# Top.net
KiCad netlist of a schematic drawn in Altium Designer
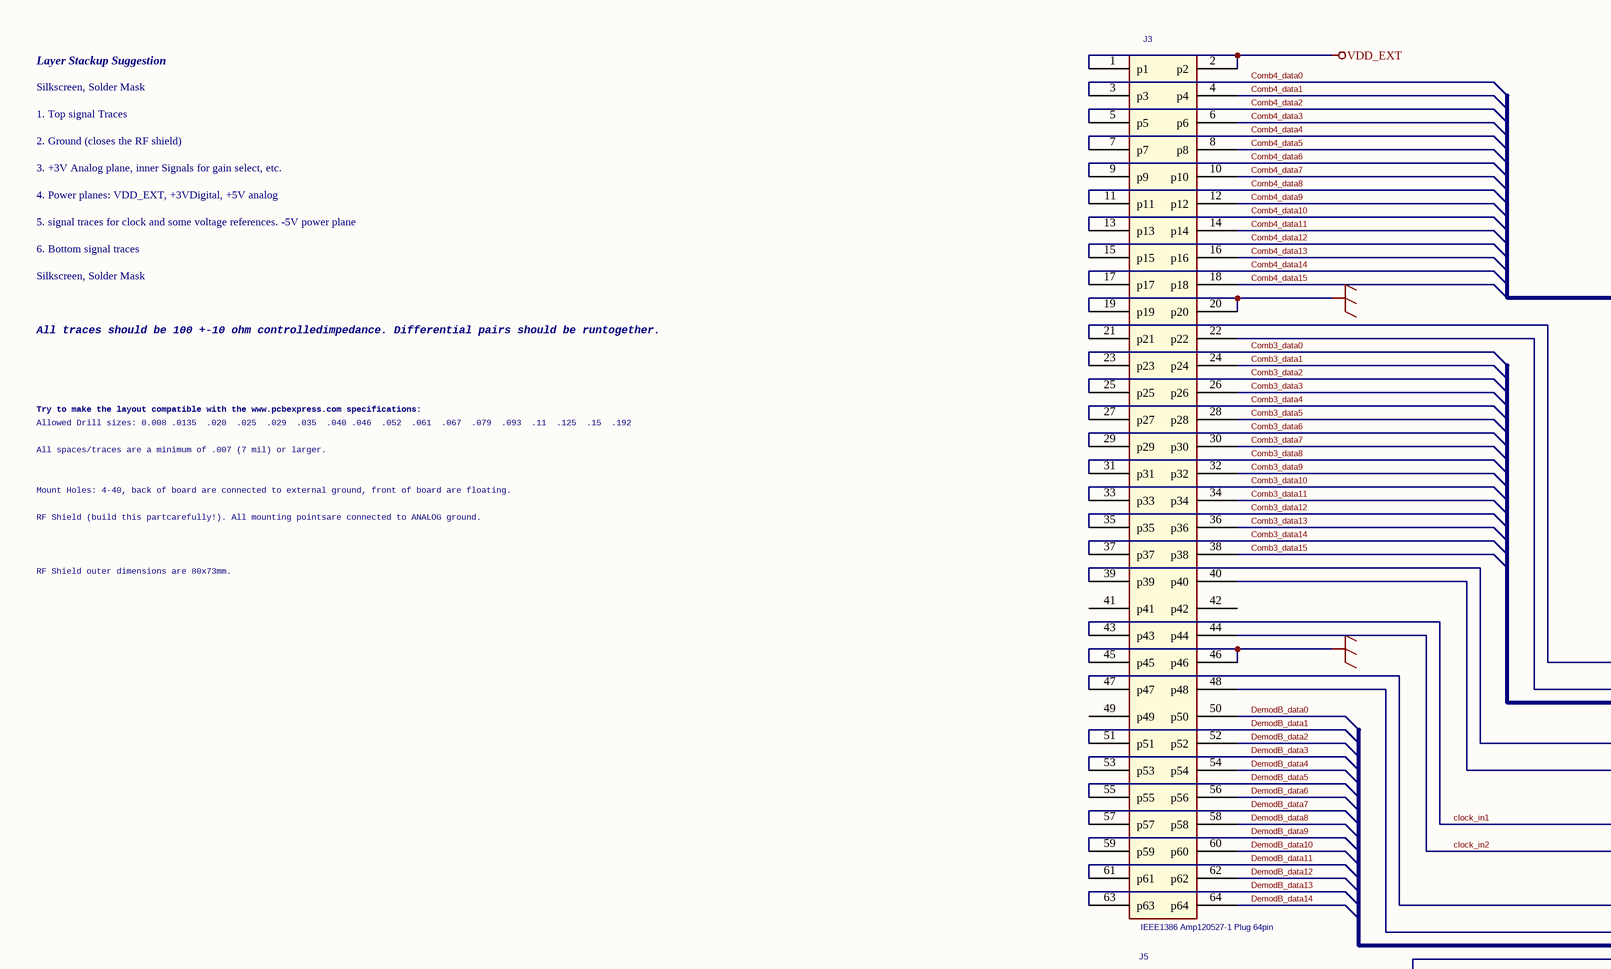
[diagram p0: Top.SchDoc, top left]
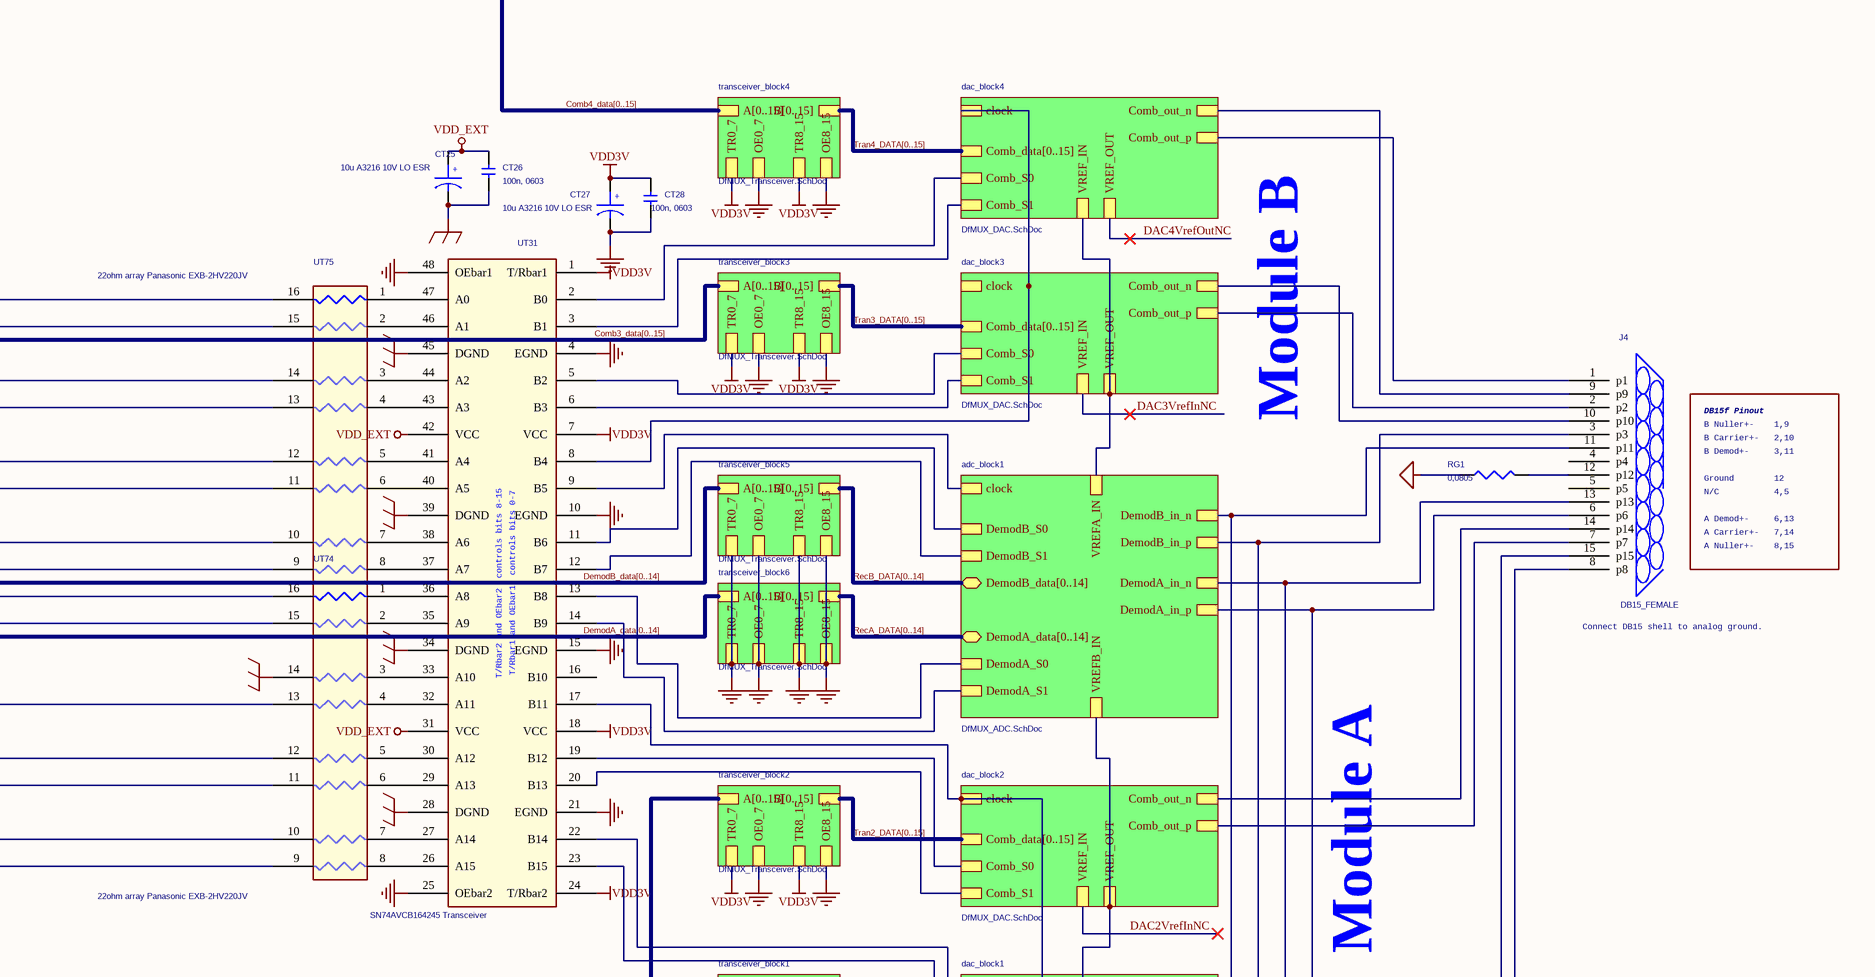
[diagram p1: Top.SchDoc, top right]
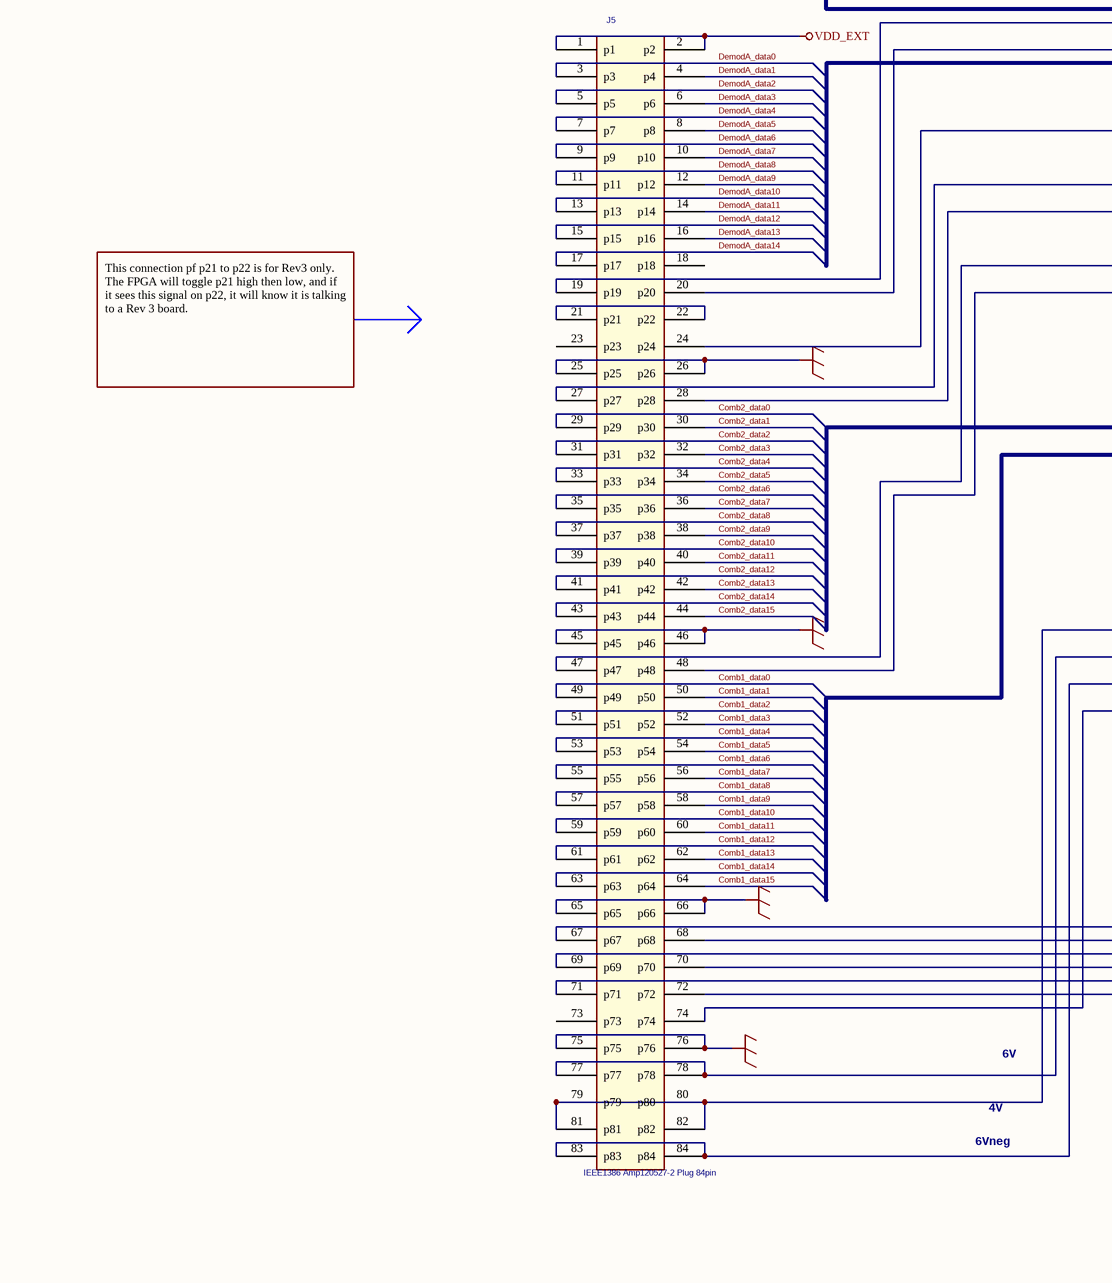
[diagram p2: Top.SchDoc, bottom left]
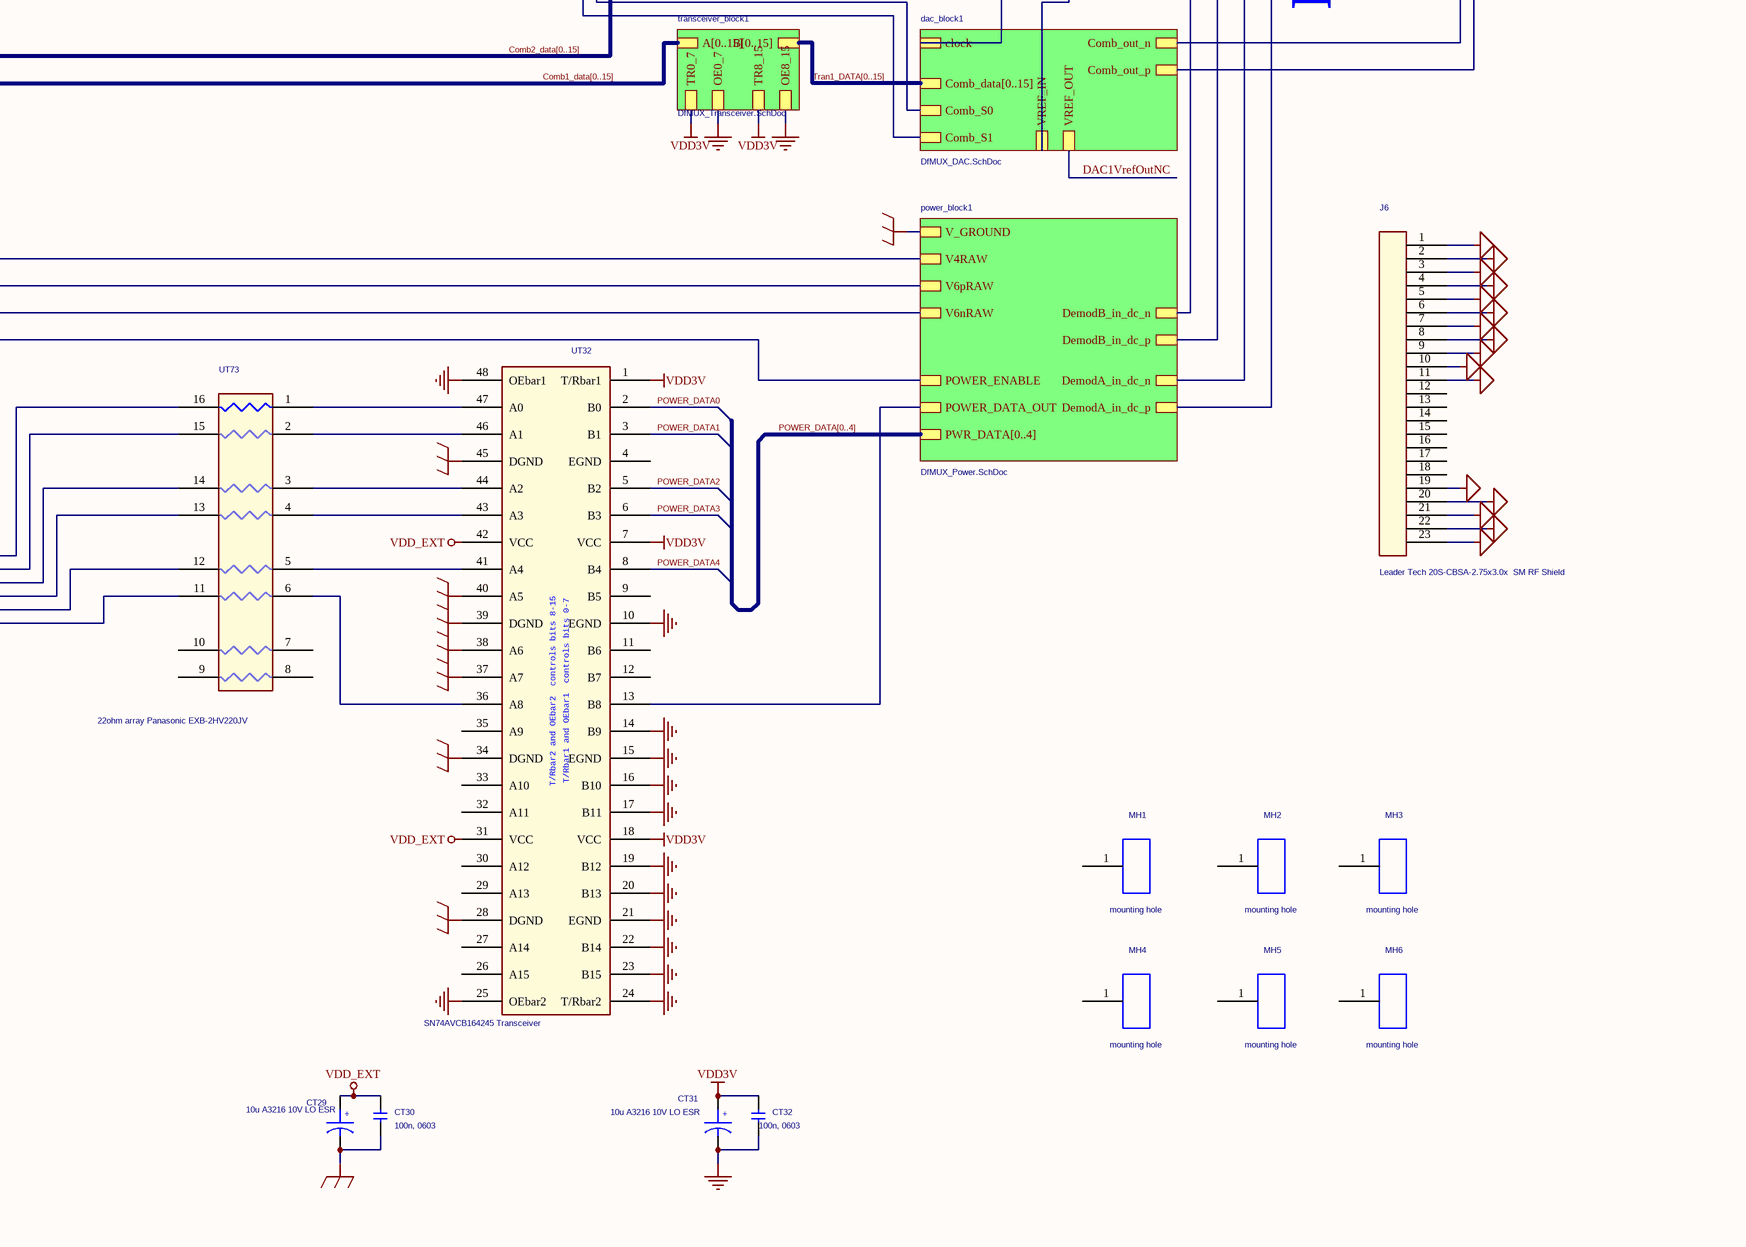
[diagram p3: Top.SchDoc, bottom right]

(export (version "E")
  (design (tool "Eeschema 10.0.6"))
  (components
    (comp (ref "CT25") (value "10u A3216 10V LO ESR") (libsource (lib "*") (part "CAPACITOR POL")))
    (comp (ref "CT26") (value "100n, 0603") (footprint "0603C") (libsource (lib "*") (part "C")))
    (comp (ref "CT27") (value "10u A3216 10V LO ESR") (libsource (lib "*") (part "CAPACITOR POL")))
    (comp (ref "CT28") (value "100n, 0603") (footprint "0603C") (libsource (lib "*") (part "C")))
    (comp (ref "CT29") (value "10u A3216 10V LO ESR") (libsource (lib "*") (part "CAPACITOR POL")))
    (comp (ref "CT30") (value "100n, 0603") (footprint "0603C") (libsource (lib "*") (part "C")))
    (comp (ref "CT31") (value "10u A3216 10V LO ESR") (libsource (lib "*") (part "CAPACITOR POL")))
    (comp (ref "CT32") (value "100n, 0603") (footprint "0603C") (libsource (lib "*") (part "C")))
    (comp (ref "J3")
      (value "IEEE1386 Amp120527-1 Plug 64pin")
      (libsource (lib "*") (part "IEEE1386 Amp120527-1 Plug 64pin"))
    )
    (comp (ref "J4") (value "DB15_FEMALE") (libsource (lib "*") (part "DB15_FEMALE")))
    (comp (ref "J5")
      (value "IEEE1386 Amp120527-2 Plug 84pin")
      (libsource (lib "*") (part "IEEE1386 Amp120527-2 Plug84pin"))
    )
    (comp (ref "J6")
      (value "Leader Tech 20S-CBSA-2.75x3.0x  SM RF Shield")
      (libsource (lib "*") (part "CONN FLEX 23"))
    )
    (comp (ref "MH1") (value "mounting hole") (libsource (lib "*") (part "SOUNDER_0")))
    (comp (ref "MH2") (value "mounting hole") (libsource (lib "*") (part "SOUNDER_0")))
    (comp (ref "MH3") (value "mounting hole") (libsource (lib "*") (part "SOUNDER_0")))
    (comp (ref "MH4") (value "mounting hole") (libsource (lib "*") (part "SOUNDER_0")))
    (comp (ref "MH5") (value "mounting hole") (libsource (lib "*") (part "SOUNDER_0")))
    (comp (ref "MH6") (value "mounting hole") (libsource (lib "*") (part "SOUNDER_0")))
    (comp (ref "RG1") (value "0,0805") (footprint "0805R") (libsource (lib "*") (part "R")))
    (comp (ref "UT31")
      (value "SN74AVCB164245 Transceiver")
      (libsource (lib "*") (part "74LVT16245 Transceiver_0"))
    )
    (comp (ref "UT32")
      (value "SN74AVCB164245 Transceiver")
      (libsource (lib "*") (part "74LVT16245 Transceiver_0"))
    )
    (comp (ref "UT73") (value "22ohm array Panasonic EXB-2HV220JV") (libsource (lib "*") (part "R-PACK_1")))
    (comp (ref "UT74") (value "22ohm array Panasonic EXB-2HV220JV") (libsource (lib "*") (part "R-PACK_1")))
    (comp (ref "UT75") (value "22ohm array Panasonic EXB-2HV220JV") (libsource (lib "*") (part "R-PACK_1")))
  )
  (nets
    (net (code "95") (name "/Comb1_data0") (class "Default")
      (node (ref "J5") (pin "49") (pinfunction "p49_49") (pintype "passive"))
    )
    (net (code "96") (name "/Comb1_data1") (class "Default")
      (node (ref "J5") (pin "50") (pinfunction "p50_50") (pintype "passive"))
    )
    (net (code "97") (name "/Comb1_data2") (class "Default")
      (node (ref "J5") (pin "51") (pinfunction "p51_51") (pintype "passive"))
    )
    (net (code "98") (name "/Comb1_data3") (class "Default")
      (node (ref "J5") (pin "52") (pinfunction "p52_52") (pintype "passive"))
    )
    (net (code "99") (name "/Comb1_data4") (class "Default")
      (node (ref "J5") (pin "53") (pinfunction "p53_53") (pintype "passive"))
    )
    (net (code "100") (name "/Comb1_data5") (class "Default")
      (node (ref "J5") (pin "54") (pinfunction "p54_54") (pintype "passive"))
    )
    (net (code "101") (name "/Comb1_data6") (class "Default")
      (node (ref "J5") (pin "55") (pinfunction "p55_55") (pintype "passive"))
    )
    (net (code "102") (name "/Comb1_data7") (class "Default")
      (node (ref "J5") (pin "56") (pinfunction "p56_56") (pintype "passive"))
    )
    (net (code "103") (name "/Comb1_data8") (class "Default")
      (node (ref "J5") (pin "57") (pinfunction "p57_57") (pintype "passive"))
    )
    (net (code "104") (name "/Comb1_data9") (class "Default")
      (node (ref "J5") (pin "58") (pinfunction "p58_58") (pintype "passive"))
    )
    (net (code "105") (name "/Comb1_data10") (class "Default")
      (node (ref "J5") (pin "59") (pinfunction "p59_59") (pintype "passive"))
    )
    (net (code "106") (name "/Comb1_data11") (class "Default")
      (node (ref "J5") (pin "60") (pinfunction "p60_60") (pintype "passive"))
    )
    (net (code "107") (name "/Comb1_data12") (class "Default")
      (node (ref "J5") (pin "61") (pinfunction "p61_61") (pintype "passive"))
    )
    (net (code "108") (name "/Comb1_data13") (class "Default")
      (node (ref "J5") (pin "62") (pinfunction "p62_62") (pintype "passive"))
    )
    (net (code "109") (name "/Comb1_data14") (class "Default")
      (node (ref "J5") (pin "63") (pinfunction "p63_63") (pintype "passive"))
    )
    (net (code "110") (name "/Comb1_data15") (class "Default")
      (node (ref "J5") (pin "64") (pinfunction "p64_64") (pintype "passive"))
    )
    (net (code "112") (name "/Comb2_data0") (class "Default")
      (node (ref "J5") (pin "29") (pinfunction "p29_29") (pintype "passive"))
    )
    (net (code "113") (name "/Comb2_data1") (class "Default")
      (node (ref "J5") (pin "30") (pinfunction "p30_30") (pintype "passive"))
    )
    (net (code "114") (name "/Comb2_data2") (class "Default")
      (node (ref "J5") (pin "31") (pinfunction "p31_31") (pintype "passive"))
    )
    (net (code "115") (name "/Comb2_data3") (class "Default")
      (node (ref "J5") (pin "32") (pinfunction "p32_32") (pintype "passive"))
    )
    (net (code "116") (name "/Comb2_data4") (class "Default")
      (node (ref "J5") (pin "33") (pinfunction "p33_33") (pintype "passive"))
    )
    (net (code "117") (name "/Comb2_data5") (class "Default")
      (node (ref "J5") (pin "34") (pinfunction "p34_34") (pintype "passive"))
    )
    (net (code "118") (name "/Comb2_data6") (class "Default")
      (node (ref "J5") (pin "35") (pinfunction "p35_35") (pintype "passive"))
    )
    (net (code "119") (name "/Comb2_data7") (class "Default")
      (node (ref "J5") (pin "36") (pinfunction "p36_36") (pintype "passive"))
    )
    (net (code "120") (name "/Comb2_data8") (class "Default")
      (node (ref "J5") (pin "37") (pinfunction "p37_37") (pintype "passive"))
    )
    (net (code "121") (name "/Comb2_data9") (class "Default")
      (node (ref "J5") (pin "38") (pinfunction "p38_38") (pintype "passive"))
    )
    (net (code "122") (name "/Comb2_data10") (class "Default")
      (node (ref "J5") (pin "39") (pinfunction "p39_39") (pintype "passive"))
    )
    (net (code "123") (name "/Comb2_data11") (class "Default")
      (node (ref "J5") (pin "40") (pinfunction "p40_40") (pintype "passive"))
    )
    (net (code "124") (name "/Comb2_data12") (class "Default")
      (node (ref "J5") (pin "41") (pinfunction "p41_41") (pintype "passive"))
    )
    (net (code "125") (name "/Comb2_data13") (class "Default")
      (node (ref "J5") (pin "42") (pinfunction "p42_42") (pintype "passive"))
    )
    (net (code "126") (name "/Comb2_data14") (class "Default")
      (node (ref "J5") (pin "43") (pinfunction "p43_43") (pintype "passive"))
    )
    (net (code "127") (name "/Comb2_data15") (class "Default")
      (node (ref "J5") (pin "44") (pinfunction "p44_44") (pintype "passive"))
    )
    (net (code "129") (name "/Comb3_data0") (class "Default")
      (node (ref "J3") (pin "23") (pinfunction "p23_23") (pintype "passive"))
    )
    (net (code "130") (name "/Comb3_data1") (class "Default")
      (node (ref "J3") (pin "24") (pinfunction "p24_24") (pintype "passive"))
    )
    (net (code "131") (name "/Comb3_data2") (class "Default")
      (node (ref "J3") (pin "25") (pinfunction "p25_25") (pintype "passive"))
    )
    (net (code "132") (name "/Comb3_data3") (class "Default")
      (node (ref "J3") (pin "26") (pinfunction "p26_26") (pintype "passive"))
    )
    (net (code "133") (name "/Comb3_data4") (class "Default")
      (node (ref "J3") (pin "27") (pinfunction "p27_27") (pintype "passive"))
    )
    (net (code "134") (name "/Comb3_data5") (class "Default")
      (node (ref "J3") (pin "28") (pinfunction "p28_28") (pintype "passive"))
    )
    (net (code "135") (name "/Comb3_data6") (class "Default")
      (node (ref "J3") (pin "29") (pinfunction "p29_29") (pintype "passive"))
    )
    (net (code "136") (name "/Comb3_data7") (class "Default")
      (node (ref "J3") (pin "30") (pinfunction "p30_30") (pintype "passive"))
    )
    (net (code "137") (name "/Comb3_data8") (class "Default")
      (node (ref "J3") (pin "31") (pinfunction "p31_31") (pintype "passive"))
    )
    (net (code "138") (name "/Comb3_data9") (class "Default")
      (node (ref "J3") (pin "32") (pinfunction "p32_32") (pintype "passive"))
    )
    (net (code "139") (name "/Comb3_data10") (class "Default")
      (node (ref "J3") (pin "33") (pinfunction "p33_33") (pintype "passive"))
    )
    (net (code "140") (name "/Comb3_data11") (class "Default")
      (node (ref "J3") (pin "34") (pinfunction "p34_34") (pintype "passive"))
    )
    (net (code "141") (name "/Comb3_data12") (class "Default")
      (node (ref "J3") (pin "35") (pinfunction "p35_35") (pintype "passive"))
    )
    (net (code "142") (name "/Comb3_data13") (class "Default")
      (node (ref "J3") (pin "36") (pinfunction "p36_36") (pintype "passive"))
    )
    (net (code "143") (name "/Comb3_data14") (class "Default")
      (node (ref "J3") (pin "37") (pinfunction "p37_37") (pintype "passive"))
    )
    (net (code "144") (name "/Comb3_data15") (class "Default")
      (node (ref "J3") (pin "38") (pinfunction "p38_38") (pintype "passive"))
    )
    (net (code "146") (name "/Comb4_data0") (class "Default")
      (node (ref "J3") (pin "3") (pinfunction "p3_3") (pintype "passive"))
    )
    (net (code "147") (name "/Comb4_data1") (class "Default")
      (node (ref "J3") (pin "4") (pinfunction "p4_4") (pintype "passive"))
    )
    (net (code "148") (name "/Comb4_data2") (class "Default")
      (node (ref "J3") (pin "5") (pinfunction "p5_5") (pintype "passive"))
    )
    (net (code "149") (name "/Comb4_data3") (class "Default")
      (node (ref "J3") (pin "6") (pinfunction "p6_6") (pintype "passive"))
    )
    (net (code "150") (name "/Comb4_data4") (class "Default")
      (node (ref "J3") (pin "7") (pinfunction "p7_7") (pintype "passive"))
    )
    (net (code "151") (name "/Comb4_data5") (class "Default")
      (node (ref "J3") (pin "8") (pinfunction "p8_8") (pintype "passive"))
    )
    (net (code "152") (name "/Comb4_data6") (class "Default")
      (node (ref "J3") (pin "9") (pinfunction "p9_9") (pintype "passive"))
    )
    (net (code "153") (name "/Comb4_data7") (class "Default")
      (node (ref "J3") (pin "10") (pinfunction "p10_10") (pintype "passive"))
    )
    (net (code "154") (name "/Comb4_data8") (class "Default")
      (node (ref "J3") (pin "11") (pinfunction "p11_11") (pintype "passive"))
    )
    (net (code "155") (name "/Comb4_data9") (class "Default")
      (node (ref "J3") (pin "12") (pinfunction "p12_12") (pintype "passive"))
    )
    (net (code "156") (name "/Comb4_data10") (class "Default")
      (node (ref "J3") (pin "13") (pinfunction "p13_13") (pintype "passive"))
    )
    (net (code "157") (name "/Comb4_data11") (class "Default")
      (node (ref "J3") (pin "14") (pinfunction "p14_14") (pintype "passive"))
    )
    (net (code "158") (name "/Comb4_data12") (class "Default")
      (node (ref "J3") (pin "15") (pinfunction "p15_15") (pintype "passive"))
    )
    (net (code "159") (name "/Comb4_data13") (class "Default")
      (node (ref "J3") (pin "16") (pinfunction "p16_16") (pintype "passive"))
    )
    (net (code "160") (name "/Comb4_data14") (class "Default")
      (node (ref "J3") (pin "17") (pinfunction "p17_17") (pintype "passive"))
    )
    (net (code "161") (name "/Comb4_data15") (class "Default")
      (node (ref "J3") (pin "18") (pinfunction "p18_18") (pintype "passive"))
    )
    (net (code "163") (name "/Comb_S0") (class "Default")
      (node (ref "UT31") (pin "19") (pinfunction "B12_19") (pintype "passive"))
    )
    (net (code "164") (name "/Comb_S0_1") (class "Default")
      (node (ref "UT31") (pin "2") (pinfunction "B0_2") (pintype "passive"))
    )
    (net (code "165") (name "/Comb_S0_2") (class "Default")
      (node (ref "UT31") (pin "5") (pinfunction "B2_5") (pintype "passive"))
    )
    (net (code "166") (name "/Comb_S0_3") (class "Default")
      (node (ref "UT31") (pin "22") (pinfunction "B14_22") (pintype "passive"))
    )
    (net (code "167") (name "/Comb_S1") (class "Default")
      (node (ref "UT31") (pin "20") (pinfunction "B13_20") (pintype "passive"))
    )
    (net (code "168") (name "/Comb_S1_1") (class "Default")
      (node (ref "UT31") (pin "3") (pinfunction "B1_3") (pintype "passive"))
    )
    (net (code "169") (name "/Comb_S1_2") (class "Default")
      (node (ref "UT31") (pin "23") (pinfunction "B15_23") (pintype "passive"))
    )
    (net (code "170") (name "/Comb_S1_3") (class "Default")
      (node (ref "UT31") (pin "6") (pinfunction "B3_6") (pintype "passive"))
    )
    (net (code "171") (name "/Comb_out_n") (class "Default")
      (node (ref "J4") (pin "15") (pinfunction "p15_15") (pintype "passive"))
    )
    (net (code "172") (name "/Comb_out_n_1") (class "Default")
      (node (ref "J4") (pin "9") (pinfunction "p9_9") (pintype "passive"))
    )
    (net (code "173") (name "/Comb_out_n_2") (class "Default")
      (node (ref "J4") (pin "10") (pinfunction "p10_10") (pintype "passive"))
    )
    (net (code "174") (name "/Comb_out_n_3") (class "Default")
      (node (ref "J4") (pin "14") (pinfunction "p14_14") (pintype "passive"))
    )
    (net (code "175") (name "/Comb_out_p") (class "Default")
      (node (ref "J4") (pin "8") (pinfunction "p8_8") (pintype "passive"))
    )
    (net (code "176") (name "/Comb_out_p_1") (class "Default")
      (node (ref "J4") (pin "1") (pinfunction "p1_1") (pintype "passive"))
    )
    (net (code "177") (name "/Comb_out_p_2") (class "Default")
      (node (ref "J4") (pin "2") (pinfunction "p2_2") (pintype "passive"))
    )
    (net (code "178") (name "/Comb_out_p_3") (class "Default")
      (node (ref "J4") (pin "7") (pinfunction "p7_7") (pintype "passive"))
    )
    (net (code "183") (name "/DemodA_S0") (class "Default")
      (node (ref "UT31") (pin "13") (pinfunction "B8_13") (pintype "passive"))
    )
    (net (code "184") (name "/DemodA_S1") (class "Default")
      (node (ref "UT31") (pin "14") (pinfunction "B9_14") (pintype "passive"))
    )
    (net (code "185") (name "/DemodA_data0") (class "Default")
      (node (ref "J5") (pin "3") (pinfunction "p3_3") (pintype "passive"))
    )
    (net (code "186") (name "/DemodA_data1") (class "Default")
      (node (ref "J5") (pin "4") (pinfunction "p4_4") (pintype "passive"))
    )
    (net (code "187") (name "/DemodA_data2") (class "Default")
      (node (ref "J5") (pin "5") (pinfunction "p5_5") (pintype "passive"))
    )
    (net (code "188") (name "/DemodA_data3") (class "Default")
      (node (ref "J5") (pin "6") (pinfunction "p6_6") (pintype "passive"))
    )
    (net (code "189") (name "/DemodA_data4") (class "Default")
      (node (ref "J5") (pin "7") (pinfunction "p7_7") (pintype "passive"))
    )
    (net (code "190") (name "/DemodA_data5") (class "Default")
      (node (ref "J5") (pin "8") (pinfunction "p8_8") (pintype "passive"))
    )
    (net (code "191") (name "/DemodA_data6") (class "Default")
      (node (ref "J5") (pin "9") (pinfunction "p9_9") (pintype "passive"))
    )
    (net (code "192") (name "/DemodA_data7") (class "Default")
      (node (ref "J5") (pin "10") (pinfunction "p10_10") (pintype "passive"))
    )
    (net (code "193") (name "/DemodA_data8") (class "Default")
      (node (ref "J5") (pin "11") (pinfunction "p11_11") (pintype "passive"))
    )
    (net (code "194") (name "/DemodA_data9") (class "Default")
      (node (ref "J5") (pin "12") (pinfunction "p12_12") (pintype "passive"))
    )
    (net (code "195") (name "/DemodA_data10") (class "Default")
      (node (ref "J5") (pin "13") (pinfunction "p13_13") (pintype "passive"))
    )
    (net (code "196") (name "/DemodA_data11") (class "Default")
      (node (ref "J5") (pin "14") (pinfunction "p14_14") (pintype "passive"))
    )
    (net (code "197") (name "/DemodA_data12") (class "Default")
      (node (ref "J5") (pin "15") (pinfunction "p15_15") (pintype "passive"))
    )
    (net (code "198") (name "/DemodA_data13") (class "Default")
      (node (ref "J5") (pin "16") (pinfunction "p16_16") (pintype "passive"))
    )
    (net (code "199") (name "/DemodA_data14") (class "Default")
      (node (ref "J5") (pin "17") (pinfunction "p17_17") (pintype "passive"))
    )
    (net (code "201") (name "/DemodA_in_dc_n") (class "Default")
      (node (ref "J4") (pin "13") (pinfunction "p13_13") (pintype "passive"))
    )
    (net (code "202") (name "/DemodA_in_dc_p") (class "Default")
      (node (ref "J4") (pin "6") (pinfunction "p6_6") (pintype "passive"))
    )
    (net (code "203") (name "/DemodB_S0") (class "Default")
      (node (ref "UT31") (pin "11") (pinfunction "B6_11") (pintype "passive"))
    )
    (net (code "204") (name "/DemodB_S1") (class "Default")
      (node (ref "UT31") (pin "12") (pinfunction "B7_12") (pintype "passive"))
    )
    (net (code "205") (name "/DemodB_data0") (class "Default")
      (node (ref "J3") (pin "50") (pinfunction "p50_50") (pintype "passive"))
    )
    (net (code "206") (name "/DemodB_data1") (class "Default")
      (node (ref "J3") (pin "51") (pinfunction "p51_51") (pintype "passive"))
    )
    (net (code "207") (name "/DemodB_data2") (class "Default")
      (node (ref "J3") (pin "52") (pinfunction "p52_52") (pintype "passive"))
    )
    (net (code "208") (name "/DemodB_data3") (class "Default")
      (node (ref "J3") (pin "53") (pinfunction "p53_53") (pintype "passive"))
    )
    (net (code "209") (name "/DemodB_data4") (class "Default")
      (node (ref "J3") (pin "54") (pinfunction "p54_54") (pintype "passive"))
    )
    (net (code "210") (name "/DemodB_data5") (class "Default")
      (node (ref "J3") (pin "55") (pinfunction "p55_55") (pintype "passive"))
    )
    (net (code "211") (name "/DemodB_data6") (class "Default")
      (node (ref "J3") (pin "56") (pinfunction "p56_56") (pintype "passive"))
    )
    (net (code "212") (name "/DemodB_data7") (class "Default")
      (node (ref "J3") (pin "57") (pinfunction "p57_57") (pintype "passive"))
    )
    (net (code "213") (name "/DemodB_data8") (class "Default")
      (node (ref "J3") (pin "58") (pinfunction "p58_58") (pintype "passive"))
    )
    (net (code "214") (name "/DemodB_data9") (class "Default")
      (node (ref "J3") (pin "59") (pinfunction "p59_59") (pintype "passive"))
    )
    (net (code "215") (name "/DemodB_data10") (class "Default")
      (node (ref "J3") (pin "60") (pinfunction "p60_60") (pintype "passive"))
    )
    (net (code "216") (name "/DemodB_data11") (class "Default")
      (node (ref "J3") (pin "61") (pinfunction "p61_61") (pintype "passive"))
    )
    (net (code "217") (name "/DemodB_data12") (class "Default")
      (node (ref "J3") (pin "62") (pinfunction "p62_62") (pintype "passive"))
    )
    (net (code "218") (name "/DemodB_data13") (class "Default")
      (node (ref "J3") (pin "63") (pinfunction "p63_63") (pintype "passive"))
    )
    (net (code "219") (name "/DemodB_data14") (class "Default")
      (node (ref "J3") (pin "64") (pinfunction "p64_64") (pintype "passive"))
    )
    (net (code "221") (name "/DemodB_in_dc_n") (class "Default")
      (node (ref "J4") (pin "11") (pinfunction "p11_11") (pintype "passive"))
    )
    (net (code "222") (name "/DemodB_in_dc_p") (class "Default")
      (node (ref "J4") (pin "3") (pinfunction "p3_3") (pintype "passive"))
    )
    (net (code "223") (name "/POWER_DATA0") (class "Default")
      (node (ref "UT32") (pin "2") (pinfunction "B0_2") (pintype "passive"))
    )
    (net (code "224") (name "/POWER_DATA1") (class "Default")
      (node (ref "UT32") (pin "3") (pinfunction "B1_3") (pintype "passive"))
    )
    (net (code "225") (name "/POWER_DATA2") (class "Default")
      (node (ref "UT32") (pin "5") (pinfunction "B2_5") (pintype "passive"))
    )
    (net (code "226") (name "/POWER_DATA3") (class "Default")
      (node (ref "UT32") (pin "6") (pinfunction "B3_6") (pintype "passive"))
    )
    (net (code "227") (name "/POWER_DATA4") (class "Default")
      (node (ref "UT32") (pin "8") (pinfunction "B4_8") (pintype "passive"))
    )
    (net (code "229") (name "/POWER_DATA_OUT") (class "Default")
      (node (ref "UT32") (pin "13") (pinfunction "B8_13") (pintype "passive"))
    )
    (net (code "230") (name "/POWER_ENABLE") (class "Default")
      (node (ref "J5") (pin "74") (pinfunction "p74_74") (pintype "passive"))
    )
    (net (code "237") (name "/V4RAW") (class "Default")
      (node (ref "J5") (pin "79") (pinfunction "p79_79") (pintype "passive"))
      (node (ref "J5") (pin "80") (pinfunction "p80_80") (pintype "passive"))
      (node (ref "J5") (pin "81") (pinfunction "p81_81") (pintype "passive"))
      (node (ref "J5") (pin "82") (pinfunction "p82_82") (pintype "passive"))
    )
    (net (code "238") (name "/V6nRAW") (class "Default")
      (node (ref "J5") (pin "83") (pinfunction "p83_83") (pintype "passive"))
      (node (ref "J5") (pin "84") (pinfunction "p84_84") (pintype "passive"))
    )
    (net (code "239") (name "/V6pRAW") (class "Default")
      (node (ref "J5") (pin "77") (pinfunction "p77_77") (pintype "passive"))
      (node (ref "J5") (pin "78") (pinfunction "p78_78") (pintype "passive"))
    )
    (net (code "242") (name "/clock") (class "Default")
      (node (ref "UT31") (pin "8") (pinfunction "B4_8") (pintype "passive"))
    )
    (net (code "243") (name "/clock_1") (class "Default")
      (node (ref "UT31") (pin "17") (pinfunction "B11_17") (pintype "passive"))
    )
    (net (code "244") (name "/clock_2") (class "Default")
      (node (ref "UT31") (pin "9") (pinfunction "B5_9") (pintype "passive"))
    )
    (net (code "245") (name "/clock_in1") (class "Default")
      (node (ref "J3") (pin "43") (pinfunction "p43_43") (pintype "passive"))
      (node (ref "UT75") (pin "12") (pinfunction "R5_12") (pintype "passive"))
    )
    (net (code "246") (name "/clock_in2") (class "Default")
      (node (ref "J3") (pin "44") (pinfunction "p44_44") (pintype "passive"))
      (node (ref "UT75") (pin "11") (pinfunction "R6_11") (pintype "passive"))
    )
    (net (code "247") (name "GND_DIG") (class "Default")
      (node (ref "CT27") (pin "2") (pinfunction "2_2") (pintype "passive"))
      (node (ref "CT28") (pin "1") (pinfunction "1_1") (pintype "passive"))
      (node (ref "CT31") (pin "2") (pinfunction "2_2") (pintype "passive"))
      (node (ref "CT32") (pin "1") (pinfunction "1_1") (pintype "passive"))
      (node (ref "UT31") (pin "10") (pinfunction "EGND_10") (pintype "passive"))
      (node (ref "UT31") (pin "15") (pinfunction "EGND_15") (pintype "passive"))
      (node (ref "UT31") (pin "21") (pinfunction "EGND_21") (pintype "passive"))
      (node (ref "UT31") (pin "25") (pinfunction "OEbar2_25") (pintype "passive"))
      (node (ref "UT31") (pin "4") (pinfunction "EGND_4") (pintype "passive"))
      (node (ref "UT31") (pin "48") (pinfunction "OEbar1_48") (pintype "passive"))
      (node (ref "UT32") (pin "10") (pinfunction "EGND_10") (pintype "passive"))
      (node (ref "UT32") (pin "14") (pinfunction "B9_14") (pintype "passive"))
      (node (ref "UT32") (pin "15") (pinfunction "EGND_15") (pintype "passive"))
      (node (ref "UT32") (pin "16") (pinfunction "B10_16") (pintype "passive"))
      (node (ref "UT32") (pin "17") (pinfunction "B11_17") (pintype "passive"))
      (node (ref "UT32") (pin "19") (pinfunction "B12_19") (pintype "passive"))
      (node (ref "UT32") (pin "20") (pinfunction "B13_20") (pintype "passive"))
      (node (ref "UT32") (pin "21") (pinfunction "EGND_21") (pintype "passive"))
      (node (ref "UT32") (pin "22") (pinfunction "B14_22") (pintype "passive"))
      (node (ref "UT32") (pin "23") (pinfunction "B15_23") (pintype "passive"))
      (node (ref "UT32") (pin "24") (pinfunction "T/Rbar2_24") (pintype "passive"))
      (node (ref "UT32") (pin "25") (pinfunction "OEbar2_25") (pintype "passive"))
      (node (ref "UT32") (pin "48") (pinfunction "OEbar1_48") (pintype "passive"))
    )
    (net (code "248") (name "GND_EARTH") (class "Default")
      (node (ref "CT25") (pin "2") (pinfunction "2_2") (pintype "passive"))
      (node (ref "CT26") (pin "1") (pinfunction "1_1") (pintype "passive"))
      (node (ref "CT29") (pin "2") (pinfunction "2_2") (pintype "passive"))
      (node (ref "CT30") (pin "1") (pinfunction "1_1") (pintype "passive"))
      (node (ref "J3") (pin "19") (pinfunction "p19_19") (pintype "passive"))
      (node (ref "J3") (pin "20") (pinfunction "p20_20") (pintype "passive"))
      (node (ref "J3") (pin "45") (pinfunction "p45_45") (pintype "passive"))
      (node (ref "J3") (pin "46") (pinfunction "p46_46") (pintype "passive"))
      (node (ref "J5") (pin "25") (pinfunction "p25_25") (pintype "passive"))
      (node (ref "J5") (pin "26") (pinfunction "p26_26") (pintype "passive"))
      (node (ref "J5") (pin "45") (pinfunction "p45_45") (pintype "passive"))
      (node (ref "J5") (pin "46") (pinfunction "p46_46") (pintype "passive"))
      (node (ref "J5") (pin "65") (pinfunction "p65_65") (pintype "passive"))
      (node (ref "J5") (pin "66") (pinfunction "p66_66") (pintype "passive"))
      (node (ref "J5") (pin "75") (pinfunction "p75_75") (pintype "passive"))
      (node (ref "J5") (pin "76") (pinfunction "p76_76") (pintype "passive"))
      (node (ref "UT31") (pin "28") (pinfunction "DGND_28") (pintype "passive"))
      (node (ref "UT31") (pin "34") (pinfunction "DGND_34") (pintype "passive"))
      (node (ref "UT31") (pin "39") (pinfunction "DGND_39") (pintype "passive"))
      (node (ref "UT31") (pin "45") (pinfunction "DGND_45") (pintype "passive"))
      (node (ref "UT32") (pin "28") (pinfunction "DGND_28") (pintype "passive"))
      (node (ref "UT32") (pin "34") (pinfunction "DGND_34") (pintype "passive"))
      (node (ref "UT32") (pin "37") (pinfunction "A7_37") (pintype "passive"))
      (node (ref "UT32") (pin "38") (pinfunction "A6_38") (pintype "passive"))
      (node (ref "UT32") (pin "39") (pinfunction "DGND_39") (pintype "passive"))
      (node (ref "UT32") (pin "40") (pinfunction "A5_40") (pintype "passive"))
      (node (ref "UT32") (pin "45") (pinfunction "DGND_45") (pintype "passive"))
      (node (ref "UT74") (pin "14") (pinfunction "R3_14") (pintype "passive"))
    )
    (net (code "249") (name "GND_SIGNAL") (class "Default")
      (node (ref "J6") (pin "1") (pinfunction "1_1") (pintype "passive"))
      (node (ref "J6") (pin "10") (pinfunction "10_10") (pintype "passive"))
      (node (ref "J6") (pin "11") (pinfunction "11_11") (pintype "passive"))
      (node (ref "J6") (pin "19") (pinfunction "19_19") (pintype "passive"))
      (node (ref "J6") (pin "2") (pinfunction "2_2") (pintype "passive"))
      (node (ref "J6") (pin "20") (pinfunction "20_20") (pintype "passive"))
      (node (ref "J6") (pin "21") (pinfunction "21_21") (pintype "passive"))
      (node (ref "J6") (pin "22") (pinfunction "22_22") (pintype "passive"))
      (node (ref "J6") (pin "23") (pinfunction "23_23") (pintype "passive"))
      (node (ref "J6") (pin "3") (pinfunction "3_3") (pintype "passive"))
      (node (ref "J6") (pin "4") (pinfunction "4_4") (pintype "passive"))
      (node (ref "J6") (pin "5") (pinfunction "5_5") (pintype "passive"))
      (node (ref "J6") (pin "6") (pinfunction "6_6") (pintype "passive"))
      (node (ref "J6") (pin "7") (pinfunction "7_7") (pintype "passive"))
      (node (ref "J6") (pin "8") (pinfunction "8_8") (pintype "passive"))
      (node (ref "J6") (pin "9") (pinfunction "9_9") (pintype "passive"))
      (node (ref "RG1") (pin "1") (pinfunction "1_1") (pintype "passive"))
    )
    (net (code "250") (name "Net-(J3-p21)") (class "Default")
      (node (ref "J3") (pin "21") (pinfunction "p21_21") (pintype "passive"))
      (node (ref "UT75") (pin "16") (pinfunction "R1_16") (pintype "passive"))
    )
    (net (code "251") (name "Net-(J3-p22)") (class "Default")
      (node (ref "J3") (pin "22") (pinfunction "p22_22") (pintype "passive"))
      (node (ref "UT75") (pin "15") (pinfunction "R2_15") (pintype "passive"))
    )
    (net (code "252") (name "Net-(J3-p39)") (class "Default")
      (node (ref "J3") (pin "39") (pinfunction "p39_39") (pintype "passive"))
      (node (ref "UT75") (pin "14") (pinfunction "R3_14") (pintype "passive"))
    )
    (net (code "253") (name "Net-(J3-p40)") (class "Default")
      (node (ref "J3") (pin "40") (pinfunction "p40_40") (pintype "passive"))
      (node (ref "UT75") (pin "13") (pinfunction "R4_13") (pintype "passive"))
    )
    (net (code "254") (name "Net-(J3-p47)") (class "Default")
      (node (ref "J3") (pin "47") (pinfunction "p47_47") (pintype "passive"))
      (node (ref "UT75") (pin "10") (pinfunction "R7_10") (pintype "passive"))
    )
    (net (code "255") (name "Net-(J3-p48)") (class "Default")
      (node (ref "J3") (pin "48") (pinfunction "p48_48") (pintype "passive"))
      (node (ref "UT75") (pin "9") (pinfunction "R8_9") (pintype "passive"))
    )
    (net (code "256") (name "Net-(J4-p12)") (class "Default")
      (node (ref "J4") (pin "12") (pinfunction "p12_12") (pintype "passive"))
      (node (ref "RG1") (pin "2") (pinfunction "2_2") (pintype "passive"))
    )
    (net (code "257") (name "Net-(J5-p19)") (class "Default")
      (node (ref "J5") (pin "19") (pinfunction "p19_19") (pintype "passive"))
      (node (ref "UT74") (pin "16") (pinfunction "R1_16") (pintype "passive"))
    )
    (net (code "258") (name "Net-(J5-p20)") (class "Default")
      (node (ref "J5") (pin "20") (pinfunction "p20_20") (pintype "passive"))
      (node (ref "UT74") (pin "15") (pinfunction "R2_15") (pintype "passive"))
    )
    (net (code "259") (name "Net-(J5-p21)") (class "Default")
      (node (ref "J5") (pin "21") (pinfunction "p21_21") (pintype "passive"))
      (node (ref "J5") (pin "22") (pinfunction "p22_22") (pintype "passive"))
    )
    (net (code "260") (name "Net-(J5-p24)") (class "Default")
      (node (ref "J5") (pin "24") (pinfunction "p24_24") (pintype "passive"))
      (node (ref "UT74") (pin "13") (pinfunction "R4_13") (pintype "passive"))
    )
    (net (code "261") (name "Net-(J5-p27)") (class "Default")
      (node (ref "J5") (pin "27") (pinfunction "p27_27") (pintype "passive"))
      (node (ref "UT74") (pin "12") (pinfunction "R5_12") (pintype "passive"))
    )
    (net (code "262") (name "Net-(J5-p28)") (class "Default")
      (node (ref "J5") (pin "28") (pinfunction "p28_28") (pintype "passive"))
      (node (ref "UT74") (pin "11") (pinfunction "R6_11") (pintype "passive"))
    )
    (net (code "263") (name "Net-(J5-p47)") (class "Default")
      (node (ref "J5") (pin "47") (pinfunction "p47_47") (pintype "passive"))
      (node (ref "UT74") (pin "10") (pinfunction "R7_10") (pintype "passive"))
    )
    (net (code "264") (name "Net-(J5-p48)") (class "Default")
      (node (ref "J5") (pin "48") (pinfunction "p48_48") (pintype "passive"))
      (node (ref "UT74") (pin "9") (pinfunction "R8_9") (pintype "passive"))
    )
    (net (code "265") (name "Net-(J5-p67)") (class "Default")
      (node (ref "J5") (pin "67") (pinfunction "p67_67") (pintype "passive"))
      (node (ref "UT73") (pin "16") (pinfunction "R1_16") (pintype "passive"))
    )
    (net (code "266") (name "Net-(J5-p68)") (class "Default")
      (node (ref "J5") (pin "68") (pinfunction "p68_68") (pintype "passive"))
      (node (ref "UT73") (pin "15") (pinfunction "R2_15") (pintype "passive"))
    )
    (net (code "267") (name "Net-(J5-p69)") (class "Default")
      (node (ref "J5") (pin "69") (pinfunction "p69_69") (pintype "passive"))
      (node (ref "UT73") (pin "14") (pinfunction "R3_14") (pintype "passive"))
    )
    (net (code "268") (name "Net-(J5-p70)") (class "Default")
      (node (ref "J5") (pin "70") (pinfunction "p70_70") (pintype "passive"))
      (node (ref "UT73") (pin "13") (pinfunction "R4_13") (pintype "passive"))
    )
    (net (code "269") (name "Net-(J5-p71)") (class "Default")
      (node (ref "J5") (pin "71") (pinfunction "p71_71") (pintype "passive"))
      (node (ref "UT73") (pin "12") (pinfunction "R5_12") (pintype "passive"))
    )
    (net (code "270") (name "Net-(J5-p72)") (class "Default")
      (node (ref "J5") (pin "72") (pinfunction "p72_72") (pintype "passive"))
      (node (ref "UT73") (pin "11") (pinfunction "R6_11") (pintype "passive"))
    )
    (net (code "271") (name "Net-(UT31-A0)") (class "Default")
      (node (ref "UT31") (pin "47") (pinfunction "A0_47") (pintype "passive"))
      (node (ref "UT75") (pin "1") (pinfunction "R1_1") (pintype "passive"))
    )
    (net (code "272") (name "Net-(UT31-A1)") (class "Default")
      (node (ref "UT31") (pin "46") (pinfunction "A1_46") (pintype "passive"))
      (node (ref "UT75") (pin "2") (pinfunction "R2_2") (pintype "passive"))
    )
    (net (code "273") (name "Net-(UT31-A2)") (class "Default")
      (node (ref "UT31") (pin "44") (pinfunction "A2_44") (pintype "passive"))
      (node (ref "UT75") (pin "3") (pinfunction "R3_3") (pintype "passive"))
    )
    (net (code "274") (name "Net-(UT31-A3)") (class "Default")
      (node (ref "UT31") (pin "43") (pinfunction "A3_43") (pintype "passive"))
      (node (ref "UT75") (pin "4") (pinfunction "R4_4") (pintype "passive"))
    )
    (net (code "275") (name "Net-(UT31-A4)") (class "Default")
      (node (ref "UT31") (pin "41") (pinfunction "A4_41") (pintype "passive"))
      (node (ref "UT75") (pin "5") (pinfunction "R5_5") (pintype "passive"))
    )
    (net (code "276") (name "Net-(UT31-A5)") (class "Default")
      (node (ref "UT31") (pin "40") (pinfunction "A5_40") (pintype "passive"))
      (node (ref "UT75") (pin "6") (pinfunction "R6_6") (pintype "passive"))
    )
    (net (code "277") (name "Net-(UT31-A6)") (class "Default")
      (node (ref "UT31") (pin "38") (pinfunction "A6_38") (pintype "passive"))
      (node (ref "UT75") (pin "7") (pinfunction "R7_7") (pintype "passive"))
    )
    (net (code "278") (name "Net-(UT31-A7)") (class "Default")
      (node (ref "UT31") (pin "37") (pinfunction "A7_37") (pintype "passive"))
      (node (ref "UT75") (pin "8") (pinfunction "R8_8") (pintype "passive"))
    )
    (net (code "279") (name "Net-(UT31-A8)") (class "Default")
      (node (ref "UT31") (pin "36") (pinfunction "A8_36") (pintype "passive"))
      (node (ref "UT74") (pin "1") (pinfunction "R1_1") (pintype "passive"))
    )
    (net (code "280") (name "Net-(UT31-A9)") (class "Default")
      (node (ref "UT31") (pin "35") (pinfunction "A9_35") (pintype "passive"))
      (node (ref "UT74") (pin "2") (pinfunction "R2_2") (pintype "passive"))
    )
    (net (code "281") (name "Net-(UT31-A10)") (class "Default")
      (node (ref "UT31") (pin "33") (pinfunction "A10_33") (pintype "passive"))
      (node (ref "UT74") (pin "3") (pinfunction "R3_3") (pintype "passive"))
    )
    (net (code "282") (name "Net-(UT31-A11)") (class "Default")
      (node (ref "UT31") (pin "32") (pinfunction "A11_32") (pintype "passive"))
      (node (ref "UT74") (pin "4") (pinfunction "R4_4") (pintype "passive"))
    )
    (net (code "283") (name "Net-(UT31-A12)") (class "Default")
      (node (ref "UT31") (pin "30") (pinfunction "A12_30") (pintype "passive"))
      (node (ref "UT74") (pin "5") (pinfunction "R5_5") (pintype "passive"))
    )
    (net (code "284") (name "Net-(UT31-A13)") (class "Default")
      (node (ref "UT31") (pin "29") (pinfunction "A13_29") (pintype "passive"))
      (node (ref "UT74") (pin "6") (pinfunction "R6_6") (pintype "passive"))
    )
    (net (code "285") (name "Net-(UT31-A14)") (class "Default")
      (node (ref "UT31") (pin "27") (pinfunction "A14_27") (pintype "passive"))
      (node (ref "UT74") (pin "7") (pinfunction "R7_7") (pintype "passive"))
    )
    (net (code "286") (name "Net-(UT31-A15)") (class "Default")
      (node (ref "UT31") (pin "26") (pinfunction "A15_26") (pintype "passive"))
      (node (ref "UT74") (pin "8") (pinfunction "R8_8") (pintype "passive"))
    )
    (net (code "287") (name "Net-(UT32-A0)") (class "Default")
      (node (ref "UT32") (pin "47") (pinfunction "A0_47") (pintype "passive"))
      (node (ref "UT73") (pin "1") (pinfunction "R1_1") (pintype "passive"))
    )
    (net (code "288") (name "Net-(UT32-A1)") (class "Default")
      (node (ref "UT32") (pin "46") (pinfunction "A1_46") (pintype "passive"))
      (node (ref "UT73") (pin "2") (pinfunction "R2_2") (pintype "passive"))
    )
    (net (code "289") (name "Net-(UT32-A2)") (class "Default")
      (node (ref "UT32") (pin "44") (pinfunction "A2_44") (pintype "passive"))
      (node (ref "UT73") (pin "3") (pinfunction "R3_3") (pintype "passive"))
    )
    (net (code "290") (name "Net-(UT32-A3)") (class "Default")
      (node (ref "UT32") (pin "43") (pinfunction "A3_43") (pintype "passive"))
      (node (ref "UT73") (pin "4") (pinfunction "R4_4") (pintype "passive"))
    )
    (net (code "291") (name "Net-(UT32-A4)") (class "Default")
      (node (ref "UT32") (pin "41") (pinfunction "A4_41") (pintype "passive"))
      (node (ref "UT73") (pin "5") (pinfunction "R5_5") (pintype "passive"))
    )
    (net (code "292") (name "Net-(UT32-A8)") (class "Default")
      (node (ref "UT32") (pin "36") (pinfunction "A8_36") (pintype "passive"))
      (node (ref "UT73") (pin "6") (pinfunction "R6_6") (pintype "passive"))
    )
    (net (code "293") (name "VDD3V") (class "Default")
      (node (ref "CT27") (pin "1") (pinfunction "1_1") (pintype "passive"))
      (node (ref "CT28") (pin "2") (pinfunction "2_2") (pintype "passive"))
      (node (ref "CT31") (pin "1") (pinfunction "1_1") (pintype "passive"))
      (node (ref "CT32") (pin "2") (pinfunction "2_2") (pintype "passive"))
      (node (ref "UT31") (pin "1") (pinfunction "T/Rbar1_1") (pintype "passive"))
      (node (ref "UT31") (pin "18") (pinfunction "VCC_18") (pintype "passive"))
      (node (ref "UT31") (pin "24") (pinfunction "T/Rbar2_24") (pintype "passive"))
      (node (ref "UT31") (pin "7") (pinfunction "VCC_7") (pintype "passive"))
      (node (ref "UT32") (pin "1") (pinfunction "T/Rbar1_1") (pintype "passive"))
      (node (ref "UT32") (pin "18") (pinfunction "VCC_18") (pintype "passive"))
      (node (ref "UT32") (pin "7") (pinfunction "VCC_7") (pintype "passive"))
    )
    (net (code "294") (name "VDD_EXT") (class "Default")
      (node (ref "CT25") (pin "1") (pinfunction "1_1") (pintype "passive"))
      (node (ref "CT26") (pin "2") (pinfunction "2_2") (pintype "passive"))
      (node (ref "CT29") (pin "1") (pinfunction "1_1") (pintype "passive"))
      (node (ref "CT30") (pin "2") (pinfunction "2_2") (pintype "passive"))
      (node (ref "J3") (pin "1") (pinfunction "p1_1") (pintype "passive"))
      (node (ref "J3") (pin "2") (pinfunction "p2_2") (pintype "passive"))
      (node (ref "J5") (pin "1") (pinfunction "p1_1") (pintype "passive"))
      (node (ref "J5") (pin "2") (pinfunction "p2_2") (pintype "passive"))
      (node (ref "UT31") (pin "31") (pinfunction "VCC_31") (pintype "passive"))
      (node (ref "UT31") (pin "42") (pinfunction "VCC_42") (pintype "passive"))
      (node (ref "UT32") (pin "31") (pinfunction "VCC_31") (pintype "passive"))
      (node (ref "UT32") (pin "42") (pinfunction "VCC_42") (pintype "passive"))
    )
    (net (code "295") (name "unconnected-(J3-p41-Pad41)") (class "Default")
      (node (ref "J3") (pin "41") (pinfunction "p41_41") (pintype "passive"))
    )
    (net (code "296") (name "unconnected-(J3-p42-Pad42)") (class "Default")
      (node (ref "J3") (pin "42") (pinfunction "p42_42") (pintype "passive"))
    )
    (net (code "297") (name "unconnected-(J3-p49-Pad49)") (class "Default")
      (node (ref "J3") (pin "49") (pinfunction "p49_49") (pintype "passive"))
    )
    (net (code "298") (name "unconnected-(J4-p4-Pad4)") (class "Default")
      (node (ref "J4") (pin "4") (pinfunction "p4_4") (pintype "passive"))
    )
    (net (code "299") (name "unconnected-(J4-p5-Pad5)") (class "Default")
      (node (ref "J4") (pin "5") (pinfunction "p5_5") (pintype "passive"))
    )
    (net (code "300") (name "unconnected-(J5-p18-Pad18)") (class "Default")
      (node (ref "J5") (pin "18") (pinfunction "p18_18") (pintype "passive"))
    )
    (net (code "301") (name "unconnected-(J5-p23-Pad23)") (class "Default")
      (node (ref "J5") (pin "23") (pinfunction "p23_23") (pintype "passive"))
    )
    (net (code "302") (name "unconnected-(J5-p73-Pad73)") (class "Default")
      (node (ref "J5") (pin "73") (pinfunction "p73_73") (pintype "passive"))
    )
    (net (code "303") (name "unconnected-(J6-Pad12)") (class "Default")
      (node (ref "J6") (pin "12") (pinfunction "12_12") (pintype "passive"))
    )
    (net (code "304") (name "unconnected-(J6-Pad13)") (class "Default")
      (node (ref "J6") (pin "13") (pinfunction "13_13") (pintype "passive"))
    )
    (net (code "305") (name "unconnected-(J6-Pad14)") (class "Default")
      (node (ref "J6") (pin "14") (pinfunction "14_14") (pintype "passive"))
    )
    (net (code "306") (name "unconnected-(J6-Pad15)") (class "Default")
      (node (ref "J6") (pin "15") (pinfunction "15_15") (pintype "passive"))
    )
    (net (code "307") (name "unconnected-(J6-Pad16)") (class "Default")
      (node (ref "J6") (pin "16") (pinfunction "16_16") (pintype "passive"))
    )
    (net (code "308") (name "unconnected-(J6-Pad17)") (class "Default")
      (node (ref "J6") (pin "17") (pinfunction "17_17") (pintype "passive"))
    )
    (net (code "309") (name "unconnected-(J6-Pad18)") (class "Default")
      (node (ref "J6") (pin "18") (pinfunction "18_18") (pintype "passive"))
    )
    (net (code "310") (name "unconnected-(MH1-A-Pad1)") (class "Default")
      (node (ref "MH1") (pin "1") (pinfunction "A_1") (pintype "passive"))
    )
    (net (code "311") (name "unconnected-(MH2-A-Pad1)") (class "Default")
      (node (ref "MH2") (pin "1") (pinfunction "A_1") (pintype "passive"))
    )
    (net (code "312") (name "unconnected-(MH3-A-Pad1)") (class "Default")
      (node (ref "MH3") (pin "1") (pinfunction "A_1") (pintype "passive"))
    )
    (net (code "313") (name "unconnected-(MH4-A-Pad1)") (class "Default")
      (node (ref "MH4") (pin "1") (pinfunction "A_1") (pintype "passive"))
    )
    (net (code "314") (name "unconnected-(MH5-A-Pad1)") (class "Default")
      (node (ref "MH5") (pin "1") (pinfunction "A_1") (pintype "passive"))
    )
    (net (code "315") (name "unconnected-(MH6-A-Pad1)") (class "Default")
      (node (ref "MH6") (pin "1") (pinfunction "A_1") (pintype "passive"))
    )
    (net (code "316") (name "unconnected-(UT31-B10-Pad16)") (class "Default")
      (node (ref "UT31") (pin "16") (pinfunction "B10_16") (pintype "passive"))
    )
    (net (code "317") (name "unconnected-(UT32-A9-Pad35)") (class "Default")
      (node (ref "UT32") (pin "35") (pinfunction "A9_35") (pintype "passive"))
    )
    (net (code "318") (name "unconnected-(UT32-A10-Pad33)") (class "Default")
      (node (ref "UT32") (pin "33") (pinfunction "A10_33") (pintype "passive"))
    )
    (net (code "319") (name "unconnected-(UT32-A11-Pad32)") (class "Default")
      (node (ref "UT32") (pin "32") (pinfunction "A11_32") (pintype "passive"))
    )
    (net (code "320") (name "unconnected-(UT32-A12-Pad30)") (class "Default")
      (node (ref "UT32") (pin "30") (pinfunction "A12_30") (pintype "passive"))
    )
    (net (code "321") (name "unconnected-(UT32-A13-Pad29)") (class "Default")
      (node (ref "UT32") (pin "29") (pinfunction "A13_29") (pintype "passive"))
    )
    (net (code "322") (name "unconnected-(UT32-A14-Pad27)") (class "Default")
      (node (ref "UT32") (pin "27") (pinfunction "A14_27") (pintype "passive"))
    )
    (net (code "323") (name "unconnected-(UT32-A15-Pad26)") (class "Default")
      (node (ref "UT32") (pin "26") (pinfunction "A15_26") (pintype "passive"))
    )
    (net (code "324") (name "unconnected-(UT32-B5-Pad9)") (class "Default")
      (node (ref "UT32") (pin "9") (pinfunction "B5_9") (pintype "passive"))
    )
    (net (code "325") (name "unconnected-(UT32-B6-Pad11)") (class "Default")
      (node (ref "UT32") (pin "11") (pinfunction "B6_11") (pintype "passive"))
    )
    (net (code "326") (name "unconnected-(UT32-B7-Pad12)") (class "Default")
      (node (ref "UT32") (pin "12") (pinfunction "B7_12") (pintype "passive"))
    )
    (net (code "327") (name "unconnected-(UT32-EGND-Pad4)") (class "Default")
      (node (ref "UT32") (pin "4") (pinfunction "EGND_4") (pintype "passive"))
    )
    (net (code "328") (name "unconnected-(UT73-R7-Pad7)") (class "Default")
      (node (ref "UT73") (pin "7") (pinfunction "R7_7") (pintype "passive"))
    )
    (net (code "329") (name "unconnected-(UT73-R7-Pad10)") (class "Default")
      (node (ref "UT73") (pin "10") (pinfunction "R7_10") (pintype "passive"))
    )
    (net (code "330") (name "unconnected-(UT73-R8-Pad8)") (class "Default")
      (node (ref "UT73") (pin "8") (pinfunction "R8_8") (pintype "passive"))
    )
    (net (code "331") (name "unconnected-(UT73-R8-Pad9)") (class "Default")
      (node (ref "UT73") (pin "9") (pinfunction "R8_9") (pintype "passive"))
    )
  )
)
